# PSCommutationRobot.net
KiCad netlist of a schematic drawn in EAGLE
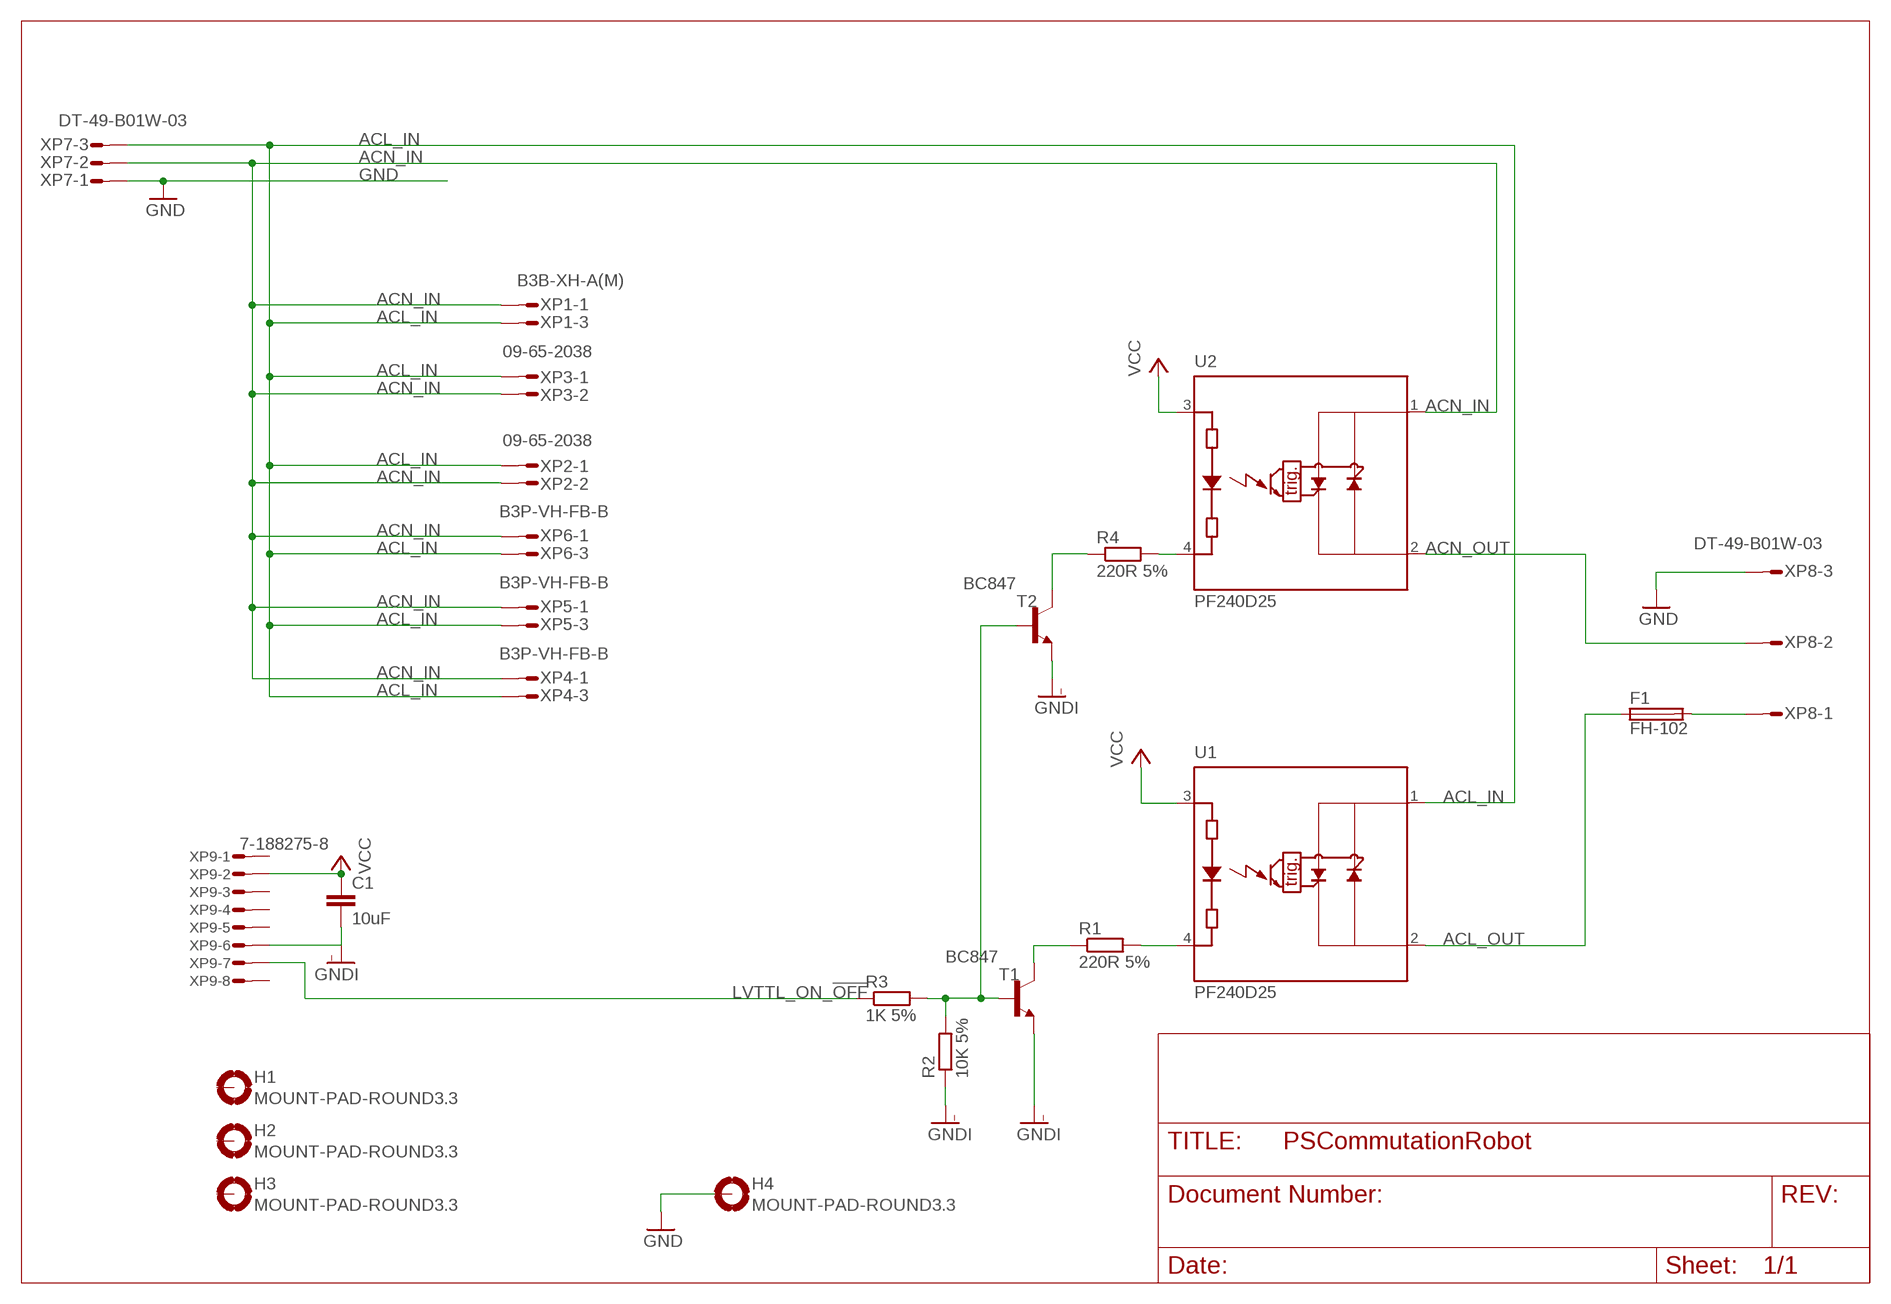
[diagram p0: schematic, sheet 1]

(export (version "E")
  (design (tool "Eeschema 10.0.6"))
  (components
    (comp (ref "C1")
      (value "10uF")
      (footprint "eagle-import:C1206")
      (libsource (lib "eagle-import") (part "C-EUC1206"))
    )
    (comp (ref "F1")
      (value "FH-102")
      (footprint "eagle-import:SH22,5A")
      (libsource (lib "eagle-import") (part "FUSESH22,5A"))
    )
    (comp (ref "H1")
      (value "MOUNT-PAD-ROUND3.3")
      (footprint "eagle-import:3,3-PAD")
      (libsource (lib "eagle-import") (part "MOUNT-PAD-ROUND3.3"))
    )
    (comp (ref "H2")
      (value "MOUNT-PAD-ROUND3.3")
      (footprint "eagle-import:3,3-PAD")
      (libsource (lib "eagle-import") (part "MOUNT-PAD-ROUND3.3"))
    )
    (comp (ref "H3")
      (value "MOUNT-PAD-ROUND3.3")
      (footprint "eagle-import:3,3-PAD")
      (libsource (lib "eagle-import") (part "MOUNT-PAD-ROUND3.3"))
    )
    (comp (ref "H4")
      (value "MOUNT-PAD-ROUND3.3")
      (footprint "eagle-import:3,3-PAD")
      (libsource (lib "eagle-import") (part "MOUNT-PAD-ROUND3.3"))
    )
    (comp (ref "R1")
      (value "220R 5%")
      (footprint "eagle-import:R0805")
      (libsource (lib "eagle-import") (part "R-EU_R0805"))
    )
    (comp (ref "R2")
      (value "10K 5%")
      (footprint "eagle-import:R0805")
      (libsource (lib "eagle-import") (part "R-EU_R0805"))
    )
    (comp (ref "R3")
      (value "1K 5%")
      (footprint "eagle-import:R0805")
      (libsource (lib "eagle-import") (part "R-EU_R0805"))
    )
    (comp (ref "R4")
      (value "220R 5%")
      (footprint "eagle-import:R0805")
      (libsource (lib "eagle-import") (part "R-EU_R0805"))
    )
    (comp (ref "T1")
      (value "BC847")
      (footprint "eagle-import:SOT23-BEC")
      (libsource (lib "eagle-import") (part "-NPN-SOT23-BECBC847"))
    )
    (comp (ref "T2")
      (value "BC847")
      (footprint "eagle-import:SOT23-BEC")
      (libsource (lib "eagle-import") (part "-NPN-SOT23-BECBC847"))
    )
    (comp (ref "U1")
      (value "PF240D25")
      (footprint "eagle-import:CRYDOM_PF240D25")
      (libsource (lib "eagle-import") (part "CRYDOM_PF240D25"))
    )
    (comp (ref "U2")
      (value "PF240D25")
      (footprint "eagle-import:CRYDOM_PF240D25")
      (libsource (lib "eagle-import") (part "CRYDOM_PF240D25"))
    )
    (comp (ref "XP1")
      (value "B3B-XH-A(M)")
      (footprint "eagle-import:JST_B3B-XH-AM")
      (libsource (lib "eagle-import") (part "B3B-XH-A(M)"))
    )
    (comp (ref "XP2")
      (value "09-65-2038")
      (footprint "eagle-import:MOLEX_09-65-2038_WITHOUT_CENTRAL_PIN")
      (libsource (lib "eagle-import") (part "MOLEX_09-65-2038_WITHOUT_CENTER_PIN"))
    )
    (comp (ref "XP3")
      (value "09-65-2038")
      (footprint "eagle-import:MOLEX_09-65-2038_WITHOUT_CENTRAL_PIN")
      (libsource (lib "eagle-import") (part "MOLEX_09-65-2038_WITHOUT_CENTER_PIN"))
    )
    (comp (ref "XP4")
      (value "B3P-VH-FB-B")
      (footprint "eagle-import:JST_B3P-VH-FB-B_WITHOUT_CENTRAL_PIN")
      (libsource (lib "eagle-import") (part "JST_B3P-VH-FB-B_WITHOUT_CENTER_PIN"))
    )
    (comp (ref "XP5")
      (value "B3P-VH-FB-B")
      (footprint "eagle-import:JST_B3P-VH-FB-B_WITHOUT_CENTRAL_PIN")
      (libsource (lib "eagle-import") (part "JST_B3P-VH-FB-B_WITHOUT_CENTER_PIN"))
    )
    (comp (ref "XP6")
      (value "B3P-VH-FB-B")
      (footprint "eagle-import:JST_B3P-VH-FB-B_WITHOUT_CENTRAL_PIN")
      (libsource (lib "eagle-import") (part "JST_B3P-VH-FB-B_WITHOUT_CENTER_PIN"))
    )
    (comp (ref "XP7")
      (value "DT-49-B01W-03")
      (footprint "eagle-import:DINKLE_DT-49-B01W-03")
      (libsource (lib "eagle-import") (part "DINKLE_DT-49-B01W-03"))
    )
    (comp (ref "XP8")
      (value "DT-49-B01W-03")
      (footprint "eagle-import:DINKLE_DT-49-B01W-03")
      (libsource (lib "eagle-import") (part "DINKLE_DT-49-B01W-03"))
    )
    (comp (ref "XP9")
      (value "7-188275-8")
      (footprint "eagle-import:MMT-F-SMD-8")
      (libsource (lib "eagle-import") (part "MICROMATCH-8SMF"))
    )
  )
  (nets
    (net (code "1") (name "/ACL_IN") (class "Default")
      (node (ref "U1") (pin "1") (pinfunction "DS1_1") (pintype "passive"))
      (node (ref "XP1") (pin "3") (pinfunction "S_3") (pintype "passive"))
      (node (ref "XP2") (pin "1") (pinfunction "S_1") (pintype "passive"))
      (node (ref "XP3") (pin "1") (pinfunction "S_1") (pintype "passive"))
      (node (ref "XP4") (pin "3") (pinfunction "S_3") (pintype "passive"))
      (node (ref "XP5") (pin "3") (pinfunction "S_3") (pintype "passive"))
      (node (ref "XP6") (pin "3") (pinfunction "S_3") (pintype "passive"))
      (node (ref "XP7") (pin "3") (pinfunction "S_3") (pintype "passive"))
    )
    (net (code "2") (name "/ACL_OUT") (class "Default")
      (node (ref "F1") (pin "1") (pinfunction "1_1") (pintype "passive"))
      (node (ref "U1") (pin "2") (pinfunction "DS2_2") (pintype "passive"))
    )
    (net (code "3") (name "/ACN_IN") (class "Default")
      (node (ref "U2") (pin "1") (pinfunction "DS1_1") (pintype "passive"))
      (node (ref "XP1") (pin "1") (pinfunction "S_1") (pintype "passive"))
      (node (ref "XP2") (pin "2") (pinfunction "S_2") (pintype "passive"))
      (node (ref "XP3") (pin "2") (pinfunction "S_2") (pintype "passive"))
      (node (ref "XP4") (pin "1") (pinfunction "S_1") (pintype "passive"))
      (node (ref "XP5") (pin "1") (pinfunction "S_1") (pintype "passive"))
      (node (ref "XP6") (pin "1") (pinfunction "S_1") (pintype "passive"))
      (node (ref "XP7") (pin "2") (pinfunction "S_2") (pintype "passive"))
    )
    (net (code "4") (name "/ACN_OUT") (class "Default")
      (node (ref "U2") (pin "2") (pinfunction "DS2_2") (pintype "passive"))
      (node (ref "XP8") (pin "2") (pinfunction "S_2") (pintype "passive"))
    )
    (net (code "5") (name "/LVTTL_ON_~{OFF}") (class "Default")
      (node (ref "R3") (pin "1") (pinfunction "1_1") (pintype "passive"))
      (node (ref "XP9") (pin "7") (pinfunction "S_7") (pintype "passive"))
    )
    (net (code "6") (name "GND") (class "Default")
      (node (ref "H4") (pin "B3,3") (pinfunction "MOUNT_B3,3") (pintype "passive"))
      (node (ref "XP7") (pin "1") (pinfunction "S_1") (pintype "passive"))
      (node (ref "XP8") (pin "3") (pinfunction "S_3") (pintype "passive"))
    )
    (net (code "7") (name "GNDI") (class "Default")
      (node (ref "C1") (pin "2") (pinfunction "2_2") (pintype "passive"))
      (node (ref "R2") (pin "1") (pinfunction "1_1") (pintype "passive"))
      (node (ref "T1") (pin "E") (pinfunction "E_E") (pintype "passive"))
      (node (ref "T2") (pin "E") (pinfunction "E_E") (pintype "passive"))
      (node (ref "XP9") (pin "6") (pinfunction "S_6") (pintype "passive"))
    )
    (net (code "8") (name "Net-(R1-Pad1)") (class "Default")
      (node (ref "R1") (pin "1") (pinfunction "1_1") (pintype "passive"))
      (node (ref "T1") (pin "C") (pinfunction "C_C") (pintype "passive"))
    )
    (net (code "9") (name "Net-(R2-Pad2)") (class "Default")
      (node (ref "R2") (pin "2") (pinfunction "2_2") (pintype "passive"))
      (node (ref "R3") (pin "2") (pinfunction "2_2") (pintype "passive"))
      (node (ref "T1") (pin "B") (pinfunction "B_B") (pintype "passive"))
      (node (ref "T2") (pin "B") (pinfunction "B_B") (pintype "passive"))
    )
    (net (code "10") (name "Net-(R4-Pad1)") (class "Default")
      (node (ref "R4") (pin "1") (pinfunction "1_1") (pintype "passive"))
      (node (ref "T2") (pin "C") (pinfunction "C_C") (pintype "passive"))
    )
    (net (code "11") (name "Net-(U1-K)") (class "Default")
      (node (ref "R1") (pin "2") (pinfunction "2_2") (pintype "passive"))
      (node (ref "U1") (pin "4") (pinfunction "K_4") (pintype "passive"))
    )
    (net (code "12") (name "Net-(U2-K)") (class "Default")
      (node (ref "R4") (pin "2") (pinfunction "2_2") (pintype "passive"))
      (node (ref "U2") (pin "4") (pinfunction "K_4") (pintype "passive"))
    )
    (net (code "13") (name "Net-(XP8A-S)") (class "Default")
      (node (ref "F1") (pin "2") (pinfunction "2_2") (pintype "passive"))
      (node (ref "XP8") (pin "1") (pinfunction "S_1") (pintype "passive"))
    )
    (net (code "14") (name "VCC") (class "Default")
      (node (ref "C1") (pin "1") (pinfunction "1_1") (pintype "passive"))
      (node (ref "U1") (pin "3") (pinfunction "A_3") (pintype "passive"))
      (node (ref "U2") (pin "3") (pinfunction "A_3") (pintype "passive"))
      (node (ref "XP9") (pin "2") (pinfunction "S_2") (pintype "passive"))
    )
    (net (code "15") (name "unconnected-(H1-MOUNT-PadB3,3)") (class "Default")
      (node (ref "H1") (pin "B3,3") (pinfunction "MOUNT_B3,3") (pintype "passive"))
    )
    (net (code "16") (name "unconnected-(H2-MOUNT-PadB3,3)") (class "Default")
      (node (ref "H2") (pin "B3,3") (pinfunction "MOUNT_B3,3") (pintype "passive"))
    )
    (net (code "17") (name "unconnected-(H3-MOUNT-PadB3,3)") (class "Default")
      (node (ref "H3") (pin "B3,3") (pinfunction "MOUNT_B3,3") (pintype "passive"))
    )
    (net (code "18") (name "unconnected-(XP9A-S-Pad1)") (class "Default")
      (node (ref "XP9") (pin "1") (pinfunction "S_1") (pintype "passive"))
    )
    (net (code "19") (name "unconnected-(XP9C-S-Pad3)") (class "Default")
      (node (ref "XP9") (pin "3") (pinfunction "S_3") (pintype "passive"))
    )
    (net (code "20") (name "unconnected-(XP9D-S-Pad4)") (class "Default")
      (node (ref "XP9") (pin "4") (pinfunction "S_4") (pintype "passive"))
    )
    (net (code "21") (name "unconnected-(XP9E-S-Pad5)") (class "Default")
      (node (ref "XP9") (pin "5") (pinfunction "S_5") (pintype "passive"))
    )
    (net (code "22") (name "unconnected-(XP9H-S-Pad8)") (class "Default")
      (node (ref "XP9") (pin "8") (pinfunction "S_8") (pintype "passive"))
    )
  )
)
